# VactrolMixer.net
KiCad netlist of a schematic drawn in EAGLE
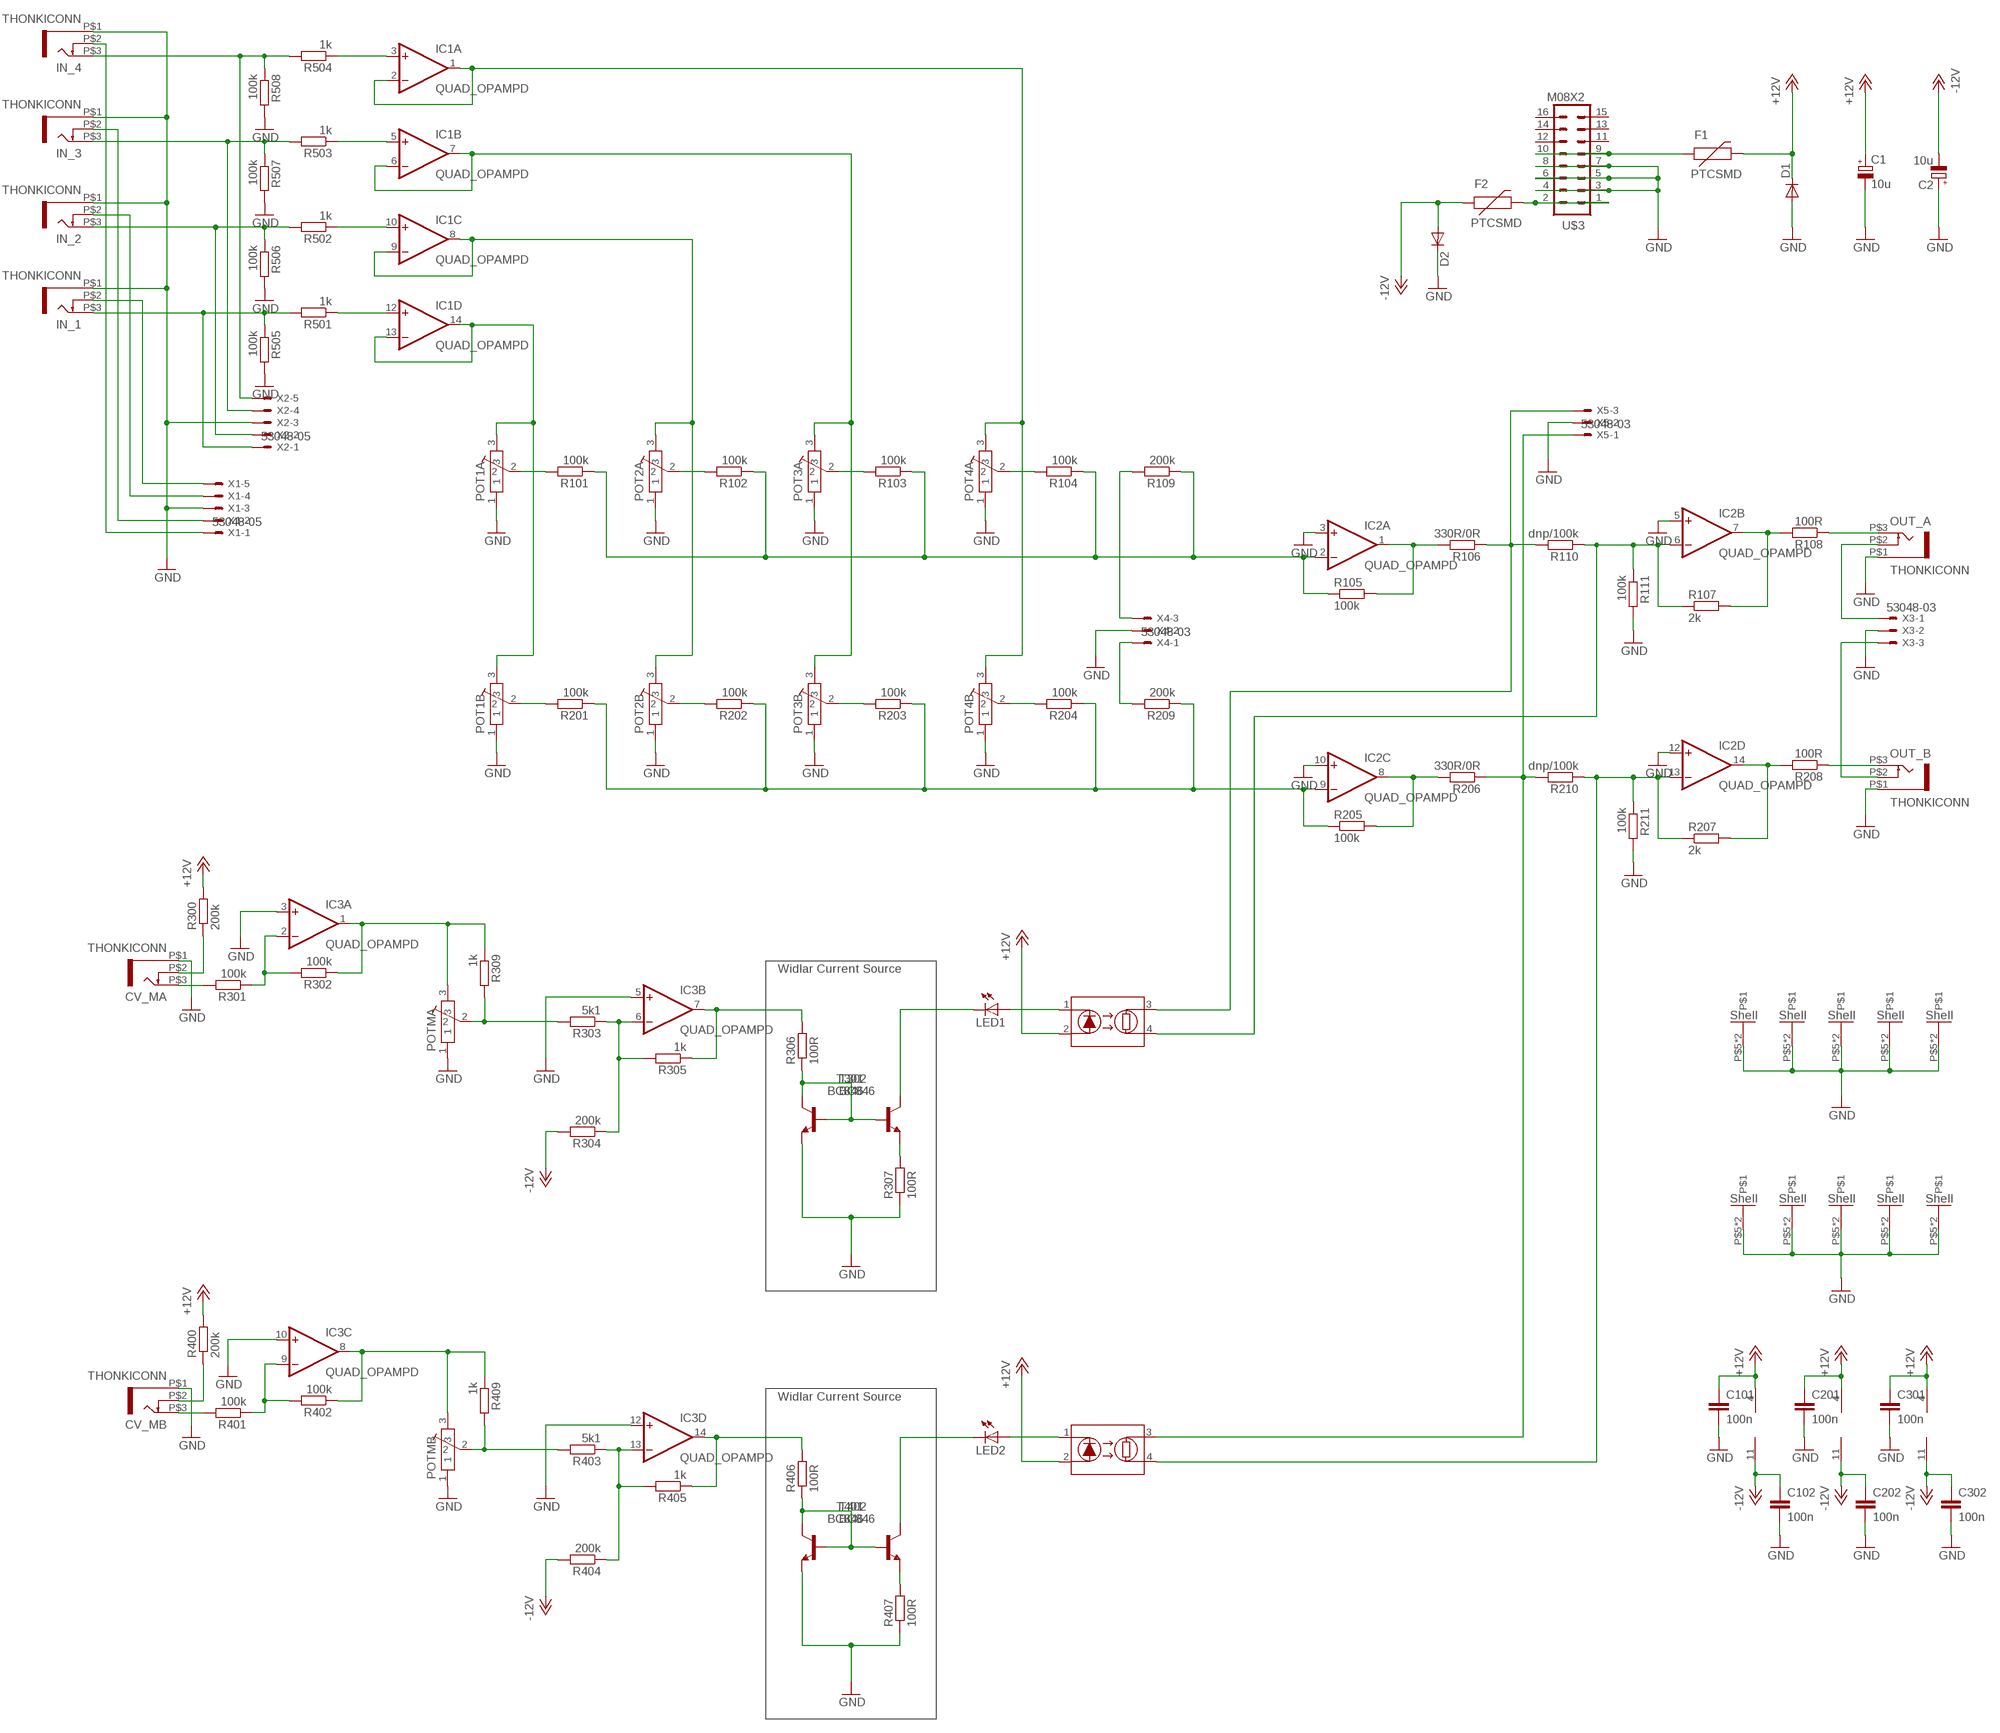
[diagram p0: schematic, sheet 1]

(export (version "E")
  (design (tool "Eeschema 10.0.6"))
  (components
    (comp (ref "C1")
      (value "10u")
      (footprint "eagle-import:153CLV-0605")
      (libsource (lib "eagle-import") (part "CPOL-EU153CLV-0605"))
    )
    (comp (ref "C2")
      (value "10u")
      (footprint "eagle-import:153CLV-0605")
      (libsource (lib "eagle-import") (part "CPOL-EU153CLV-0605"))
    )
    (comp (ref "C101")
      (value "100n")
      (footprint "eagle-import:C0603")
      (libsource (lib "eagle-import") (part "C-EUC0603"))
    )
    (comp (ref "C102")
      (value "100n")
      (footprint "eagle-import:C0603")
      (libsource (lib "eagle-import") (part "C-EUC0603"))
    )
    (comp (ref "C201")
      (value "100n")
      (footprint "eagle-import:C0603")
      (libsource (lib "eagle-import") (part "C-EUC0603"))
    )
    (comp (ref "C202")
      (value "100n")
      (footprint "eagle-import:C0603")
      (libsource (lib "eagle-import") (part "C-EUC0603"))
    )
    (comp (ref "C301")
      (value "100n")
      (footprint "eagle-import:C0603")
      (libsource (lib "eagle-import") (part "C-EUC0603"))
    )
    (comp (ref "C302")
      (value "100n")
      (footprint "eagle-import:C0603")
      (libsource (lib "eagle-import") (part "C-EUC0603"))
    )
    (comp (ref "CV_MA")
      (value "THONKICONN")
      (footprint "eagle-import:THONKICONN")
      (libsource (lib "eagle-import") (part "THONKICONN"))
    )
    (comp (ref "CV_MB")
      (value "THONKICONN")
      (footprint "eagle-import:THONKICONN")
      (libsource (lib "eagle-import") (part "THONKICONN"))
    )
    (comp (ref "D1")
      (value "DIODESMA")
      (footprint "eagle-import:SMA-DIODE")
      (libsource (lib "eagle-import") (part "DIODESMA"))
    )
    (comp (ref "D2")
      (value "DIODESMA")
      (footprint "eagle-import:SMA-DIODE")
      (libsource (lib "eagle-import") (part "DIODESMA"))
    )
    (comp (ref "F1")
      (value "PTCSMD")
      (footprint "eagle-import:PTC-1206")
      (libsource (lib "eagle-import") (part "PTCSMD"))
    )
    (comp (ref "F2")
      (value "PTCSMD")
      (footprint "eagle-import:PTC-1206")
      (libsource (lib "eagle-import") (part "PTCSMD"))
    )
    (comp (ref "IC1")
      (value "QUAD_OPAMPD")
      (footprint "eagle-import:SO14")
      (libsource (lib "eagle-import") (part "QUAD_OPAMPD"))
    )
    (comp (ref "IC2")
      (value "QUAD_OPAMPD")
      (footprint "eagle-import:SO14")
      (libsource (lib "eagle-import") (part "QUAD_OPAMPD"))
    )
    (comp (ref "IC3")
      (value "QUAD_OPAMPD")
      (footprint "eagle-import:SO14")
      (libsource (lib "eagle-import") (part "QUAD_OPAMPD"))
    )
    (comp (ref "IN_1")
      (value "THONKICONN")
      (footprint "eagle-import:THONKICONN")
      (libsource (lib "eagle-import") (part "THONKICONN"))
    )
    (comp (ref "IN_2")
      (value "THONKICONN")
      (footprint "eagle-import:THONKICONN")
      (libsource (lib "eagle-import") (part "THONKICONN"))
    )
    (comp (ref "IN_3")
      (value "THONKICONN")
      (footprint "eagle-import:THONKICONN")
      (libsource (lib "eagle-import") (part "THONKICONN"))
    )
    (comp (ref "IN_4")
      (value "THONKICONN")
      (footprint "eagle-import:THONKICONN")
      (libsource (lib "eagle-import") (part "THONKICONN"))
    )
    (comp (ref "LED1")
      (value "LED3MM")
      (footprint "eagle-import:LED3MM")
      (libsource (lib "eagle-import") (part "LED3MM"))
    )
    (comp (ref "LED2")
      (value "LED3MM")
      (footprint "eagle-import:LED3MM")
      (libsource (lib "eagle-import") (part "LED3MM"))
    )
    (comp (ref "OUT_A")
      (value "THONKICONN")
      (footprint "eagle-import:THONKICONN")
      (libsource (lib "eagle-import") (part "THONKICONN"))
    )
    (comp (ref "OUT_B")
      (value "THONKICONN")
      (footprint "eagle-import:THONKICONN")
      (libsource (lib "eagle-import") (part "THONKICONN"))
    )
    (comp (ref "POT1A")
      (value "POT-ALPS-RK09L1140")
      (footprint "eagle-import:POT-ALPS-RK09L1140")
      (libsource (lib "eagle-import") (part "POT-ALPS-RK09L1140"))
    )
    (comp (ref "POT1B")
      (value "POT-ALPS-RK09L1140")
      (footprint "eagle-import:POT-ALPS-RK09L1140")
      (libsource (lib "eagle-import") (part "POT-ALPS-RK09L1140"))
    )
    (comp (ref "POT2A")
      (value "POT-ALPS-RK09L1140")
      (footprint "eagle-import:POT-ALPS-RK09L1140")
      (libsource (lib "eagle-import") (part "POT-ALPS-RK09L1140"))
    )
    (comp (ref "POT2B")
      (value "POT-ALPS-RK09L1140")
      (footprint "eagle-import:POT-ALPS-RK09L1140")
      (libsource (lib "eagle-import") (part "POT-ALPS-RK09L1140"))
    )
    (comp (ref "POT3A")
      (value "POT-ALPS-RK09L1140")
      (footprint "eagle-import:POT-ALPS-RK09L1140")
      (libsource (lib "eagle-import") (part "POT-ALPS-RK09L1140"))
    )
    (comp (ref "POT3B")
      (value "POT-ALPS-RK09L1140")
      (footprint "eagle-import:POT-ALPS-RK09L1140")
      (libsource (lib "eagle-import") (part "POT-ALPS-RK09L1140"))
    )
    (comp (ref "POT4A")
      (value "POT-ALPS-RK09L1140")
      (footprint "eagle-import:POT-ALPS-RK09L1140")
      (libsource (lib "eagle-import") (part "POT-ALPS-RK09L1140"))
    )
    (comp (ref "POT4B")
      (value "POT-ALPS-RK09L1140")
      (footprint "eagle-import:POT-ALPS-RK09L1140")
      (libsource (lib "eagle-import") (part "POT-ALPS-RK09L1140"))
    )
    (comp (ref "POTMA")
      (value "POT-ALPS-RK09L1140")
      (footprint "eagle-import:POT-ALPS-RK09L1140")
      (libsource (lib "eagle-import") (part "POT-ALPS-RK09L1140"))
    )
    (comp (ref "POTMB")
      (value "POT-ALPS-RK09L1140")
      (footprint "eagle-import:POT-ALPS-RK09L1140")
      (libsource (lib "eagle-import") (part "POT-ALPS-RK09L1140"))
    )
    (comp (ref "R101")
      (value "100k")
      (footprint "eagle-import:R0603")
      (libsource (lib "eagle-import") (part "R-EU_R0603"))
    )
    (comp (ref "R102")
      (value "100k")
      (footprint "eagle-import:R0603")
      (libsource (lib "eagle-import") (part "R-EU_R0603"))
    )
    (comp (ref "R103")
      (value "100k")
      (footprint "eagle-import:R0603")
      (libsource (lib "eagle-import") (part "R-EU_R0603"))
    )
    (comp (ref "R104")
      (value "100k")
      (footprint "eagle-import:R0603")
      (libsource (lib "eagle-import") (part "R-EU_R0603"))
    )
    (comp (ref "R105")
      (value "100k")
      (footprint "eagle-import:R0603")
      (libsource (lib "eagle-import") (part "R-EU_R0603"))
    )
    (comp (ref "R106")
      (value "330R/0R")
      (footprint "eagle-import:R0603")
      (libsource (lib "eagle-import") (part "R-EU_R0603"))
    )
    (comp (ref "R107")
      (value "2k")
      (footprint "eagle-import:R0603")
      (libsource (lib "eagle-import") (part "R-EU_R0603"))
    )
    (comp (ref "R108")
      (value "100R")
      (footprint "eagle-import:R0603")
      (libsource (lib "eagle-import") (part "R-EU_R0603"))
    )
    (comp (ref "R109")
      (value "200k")
      (footprint "eagle-import:R0603")
      (libsource (lib "eagle-import") (part "R-EU_R0603"))
    )
    (comp (ref "R110")
      (value "dnp/100k")
      (footprint "eagle-import:R0603")
      (libsource (lib "eagle-import") (part "R-EU_R0603"))
    )
    (comp (ref "R111")
      (value "100k")
      (footprint "eagle-import:R0603")
      (libsource (lib "eagle-import") (part "R-EU_R0603"))
    )
    (comp (ref "R201")
      (value "100k")
      (footprint "eagle-import:R0603")
      (libsource (lib "eagle-import") (part "R-EU_R0603"))
    )
    (comp (ref "R202")
      (value "100k")
      (footprint "eagle-import:R0603")
      (libsource (lib "eagle-import") (part "R-EU_R0603"))
    )
    (comp (ref "R203")
      (value "100k")
      (footprint "eagle-import:R0603")
      (libsource (lib "eagle-import") (part "R-EU_R0603"))
    )
    (comp (ref "R204")
      (value "100k")
      (footprint "eagle-import:R0603")
      (libsource (lib "eagle-import") (part "R-EU_R0603"))
    )
    (comp (ref "R205")
      (value "100k")
      (footprint "eagle-import:R0603")
      (libsource (lib "eagle-import") (part "R-EU_R0603"))
    )
    (comp (ref "R206")
      (value "330R/0R")
      (footprint "eagle-import:R0603")
      (libsource (lib "eagle-import") (part "R-EU_R0603"))
    )
    (comp (ref "R207")
      (value "2k")
      (footprint "eagle-import:R0603")
      (libsource (lib "eagle-import") (part "R-EU_R0603"))
    )
    (comp (ref "R208")
      (value "100R")
      (footprint "eagle-import:R0603")
      (libsource (lib "eagle-import") (part "R-EU_R0603"))
    )
    (comp (ref "R209")
      (value "200k")
      (footprint "eagle-import:R0603")
      (libsource (lib "eagle-import") (part "R-EU_R0603"))
    )
    (comp (ref "R210")
      (value "dnp/100k")
      (footprint "eagle-import:R0603")
      (libsource (lib "eagle-import") (part "R-EU_R0603"))
    )
    (comp (ref "R211")
      (value "100k")
      (footprint "eagle-import:R0603")
      (libsource (lib "eagle-import") (part "R-EU_R0603"))
    )
    (comp (ref "R300")
      (value "200k")
      (footprint "eagle-import:R0603")
      (libsource (lib "eagle-import") (part "R-EU_R0603"))
    )
    (comp (ref "R301")
      (value "100k")
      (footprint "eagle-import:R0603")
      (libsource (lib "eagle-import") (part "R-EU_R0603"))
    )
    (comp (ref "R302")
      (value "100k")
      (footprint "eagle-import:R0603")
      (libsource (lib "eagle-import") (part "R-EU_R0603"))
    )
    (comp (ref "R303")
      (value "5k1")
      (footprint "eagle-import:R0603")
      (libsource (lib "eagle-import") (part "R-EU_R0603"))
    )
    (comp (ref "R304")
      (value "200k")
      (footprint "eagle-import:R0603")
      (libsource (lib "eagle-import") (part "R-EU_R0603"))
    )
    (comp (ref "R305")
      (value "1k")
      (footprint "eagle-import:R0603")
      (libsource (lib "eagle-import") (part "R-EU_R0603"))
    )
    (comp (ref "R306")
      (value "100R")
      (footprint "eagle-import:R0603")
      (libsource (lib "eagle-import") (part "R-EU_R0603"))
    )
    (comp (ref "R307")
      (value "100R")
      (footprint "eagle-import:R0603")
      (libsource (lib "eagle-import") (part "R-EU_R0603"))
    )
    (comp (ref "R309")
      (value "1k")
      (footprint "eagle-import:R0603")
      (libsource (lib "eagle-import") (part "R-EU_R0603"))
    )
    (comp (ref "R400")
      (value "200k")
      (footprint "eagle-import:R0603")
      (libsource (lib "eagle-import") (part "R-EU_R0603"))
    )
    (comp (ref "R401")
      (value "100k")
      (footprint "eagle-import:R0603")
      (libsource (lib "eagle-import") (part "R-EU_R0603"))
    )
    (comp (ref "R402")
      (value "100k")
      (footprint "eagle-import:R0603")
      (libsource (lib "eagle-import") (part "R-EU_R0603"))
    )
    (comp (ref "R403")
      (value "5k1")
      (footprint "eagle-import:R0603")
      (libsource (lib "eagle-import") (part "R-EU_R0603"))
    )
    (comp (ref "R404")
      (value "200k")
      (footprint "eagle-import:R0603")
      (libsource (lib "eagle-import") (part "R-EU_R0603"))
    )
    (comp (ref "R405")
      (value "1k")
      (footprint "eagle-import:R0603")
      (libsource (lib "eagle-import") (part "R-EU_R0603"))
    )
    (comp (ref "R406")
      (value "100R")
      (footprint "eagle-import:R0603")
      (libsource (lib "eagle-import") (part "R-EU_R0603"))
    )
    (comp (ref "R407")
      (value "100R")
      (footprint "eagle-import:R0603")
      (libsource (lib "eagle-import") (part "R-EU_R0603"))
    )
    (comp (ref "R409")
      (value "1k")
      (footprint "eagle-import:R0603")
      (libsource (lib "eagle-import") (part "R-EU_R0603"))
    )
    (comp (ref "R501")
      (value "1k")
      (footprint "eagle-import:R0603")
      (libsource (lib "eagle-import") (part "R-EU_R0603"))
    )
    (comp (ref "R502")
      (value "1k")
      (footprint "eagle-import:R0603")
      (libsource (lib "eagle-import") (part "R-EU_R0603"))
    )
    (comp (ref "R503")
      (value "1k")
      (footprint "eagle-import:R0603")
      (libsource (lib "eagle-import") (part "R-EU_R0603"))
    )
    (comp (ref "R504")
      (value "1k")
      (footprint "eagle-import:R0603")
      (libsource (lib "eagle-import") (part "R-EU_R0603"))
    )
    (comp (ref "R505")
      (value "100k")
      (footprint "eagle-import:R0603")
      (libsource (lib "eagle-import") (part "R-EU_R0603"))
    )
    (comp (ref "R506")
      (value "100k")
      (footprint "eagle-import:R0603")
      (libsource (lib "eagle-import") (part "R-EU_R0603"))
    )
    (comp (ref "R507")
      (value "100k")
      (footprint "eagle-import:R0603")
      (libsource (lib "eagle-import") (part "R-EU_R0603"))
    )
    (comp (ref "R508")
      (value "100k")
      (footprint "eagle-import:R0603")
      (libsource (lib "eagle-import") (part "R-EU_R0603"))
    )
    (comp (ref "T301")
      (value "BC846")
      (footprint "eagle-import:SOT23")
      (libsource (lib "eagle-import") (part "BC846"))
    )
    (comp (ref "T302")
      (value "BC846")
      (footprint "eagle-import:SOT23")
      (libsource (lib "eagle-import") (part "BC846"))
    )
    (comp (ref "T401")
      (value "BC846")
      (footprint "eagle-import:SOT23")
      (libsource (lib "eagle-import") (part "BC846"))
    )
    (comp (ref "T402")
      (value "BC846")
      (footprint "eagle-import:SOT23")
      (libsource (lib "eagle-import") (part "BC846"))
    )
    (comp (ref "U$3")
      (value "M08X2")
      (footprint "eagle-import:2X8")
      (libsource (lib "eagle-import") (part "M08X2"))
    )
    (comp (ref "VAC1")
      (value "VTL5C3")
      (footprint "eagle-import:VTL5C3")
      (libsource (lib "eagle-import") (part "VTL5C3"))
    )
    (comp (ref "VAC2")
      (value "VTL5C3")
      (footprint "eagle-import:VTL5C3")
      (libsource (lib "eagle-import") (part "VTL5C3"))
    )
    (comp (ref "X1")
      (value "53048-05")
      (footprint "eagle-import:53048-05")
      (fields (field (name "MF") "MOLEX") (field (name "MPN") "53048-0510"))
      (libsource (lib "eagle-import") (part "53?-05048"))
    )
    (comp (ref "X2")
      (value "53048-05")
      (footprint "eagle-import:53048-05")
      (fields (field (name "MF") "MOLEX") (field (name "MPN") "53048-0510"))
      (libsource (lib "eagle-import") (part "53?-05048"))
    )
    (comp (ref "X3")
      (value "53048-03")
      (footprint "eagle-import:53048-03")
      (fields (field (name "MF") "WALDOM/MOLEX") (field (name "MPN") "53048-0310"))
      (libsource (lib "eagle-import") (part "53?-03048"))
    )
    (comp (ref "X4")
      (value "53048-03")
      (footprint "eagle-import:53048-03")
      (fields (field (name "MF") "WALDOM/MOLEX") (field (name "MPN") "53048-0310"))
      (libsource (lib "eagle-import") (part "53?-03048"))
    )
    (comp (ref "X5")
      (value "53048-03")
      (footprint "eagle-import:53048-03")
      (fields (field (name "MF") "WALDOM/MOLEX") (field (name "MPN") "53048-0310"))
      (libsource (lib "eagle-import") (part "53?-03048"))
    )
  )
  (nets
    (net (code "1") (name "+12V") (class "Default")
      (node (ref "C1") (pin "+") (pinfunction "+_+") (pintype "passive"))
      (node (ref "C101") (pin "1") (pinfunction "1_1") (pintype "passive"))
      (node (ref "C201") (pin "1") (pinfunction "1_1") (pintype "passive"))
      (node (ref "C301") (pin "1") (pinfunction "1_1") (pintype "passive"))
      (node (ref "D1") (pin "C") (pinfunction "C_C") (pintype "passive"))
      (node (ref "F1") (pin "2") (pinfunction "2_2") (pintype "bidirectional"))
      (node (ref "IC1") (pin "4") (pinfunction "V+_4") (pintype "power_in"))
      (node (ref "IC2") (pin "4") (pinfunction "V+_4") (pintype "power_in"))
      (node (ref "IC3") (pin "4") (pinfunction "V+_4") (pintype "power_in"))
      (node (ref "R300") (pin "2") (pinfunction "2_2") (pintype "passive"))
      (node (ref "R400") (pin "2") (pinfunction "2_2") (pintype "passive"))
      (node (ref "VAC1") (pin "2") (pinfunction "LED+_2") (pintype "bidirectional"))
      (node (ref "VAC2") (pin "2") (pinfunction "LED+_2") (pintype "bidirectional"))
    )
    (net (code "2") (name "-12V") (class "Default")
      (node (ref "C102") (pin "1") (pinfunction "1_1") (pintype "passive"))
      (node (ref "C2") (pin "-") (pinfunction "-_-") (pintype "passive"))
      (node (ref "C202") (pin "1") (pinfunction "1_1") (pintype "passive"))
      (node (ref "C302") (pin "1") (pinfunction "1_1") (pintype "passive"))
      (node (ref "D2") (pin "A") (pinfunction "A_A") (pintype "passive"))
      (node (ref "F2") (pin "1") (pinfunction "1_1") (pintype "bidirectional"))
      (node (ref "IC1") (pin "11") (pinfunction "V-_11") (pintype "power_in"))
      (node (ref "IC2") (pin "11") (pinfunction "V-_11") (pintype "power_in"))
      (node (ref "IC3") (pin "11") (pinfunction "V-_11") (pintype "power_in"))
      (node (ref "R304") (pin "2") (pinfunction "2_2") (pintype "passive"))
      (node (ref "R404") (pin "2") (pinfunction "2_2") (pintype "passive"))
    )
    (net (code "3") (name "GND") (class "Default")
      (node (ref "C1") (pin "-") (pinfunction "-_-") (pintype "passive"))
      (node (ref "C101") (pin "2") (pinfunction "2_2") (pintype "passive"))
      (node (ref "C102") (pin "2") (pinfunction "2_2") (pintype "passive"))
      (node (ref "C2") (pin "+") (pinfunction "+_+") (pintype "passive"))
      (node (ref "C201") (pin "2") (pinfunction "2_2") (pintype "passive"))
      (node (ref "C202") (pin "2") (pinfunction "2_2") (pintype "passive"))
      (node (ref "C301") (pin "2") (pinfunction "2_2") (pintype "passive"))
      (node (ref "C302") (pin "2") (pinfunction "2_2") (pintype "passive"))
      (node (ref "CV_MA") (pin "P$1") (pinfunction "5_P$1") (pintype "passive"))
      (node (ref "CV_MB") (pin "P$1") (pinfunction "5_P$1") (pintype "passive"))
      (node (ref "D1") (pin "A") (pinfunction "A_A") (pintype "passive"))
      (node (ref "D2") (pin "C") (pinfunction "C_C") (pintype "passive"))
      (node (ref "IC2") (pin "10") (pinfunction "+IN_10") (pintype "input"))
      (node (ref "IC2") (pin "12") (pinfunction "+IN_12") (pintype "input"))
      (node (ref "IC2") (pin "3") (pinfunction "+IN_3") (pintype "input"))
      (node (ref "IC2") (pin "5") (pinfunction "+IN_5") (pintype "input"))
      (node (ref "IC3") (pin "10") (pinfunction "+IN_10") (pintype "input"))
      (node (ref "IC3") (pin "12") (pinfunction "+IN_12") (pintype "input"))
      (node (ref "IC3") (pin "3") (pinfunction "+IN_3") (pintype "input"))
      (node (ref "IC3") (pin "5") (pinfunction "+IN_5") (pintype "input"))
      (node (ref "IN_1") (pin "P$1") (pinfunction "5_P$1") (pintype "passive"))
      (node (ref "IN_2") (pin "P$1") (pinfunction "5_P$1") (pintype "passive"))
      (node (ref "IN_3") (pin "P$1") (pinfunction "5_P$1") (pintype "passive"))
      (node (ref "IN_4") (pin "P$1") (pinfunction "5_P$1") (pintype "passive"))
      (node (ref "OUT_A") (pin "P$1") (pinfunction "5_P$1") (pintype "passive"))
      (node (ref "OUT_B") (pin "P$1") (pinfunction "5_P$1") (pintype "passive"))
      (node (ref "POT1A") (pin "1") (pinfunction "1_1") (pintype "bidirectional"))
      (node (ref "POT1A") (pin "P$5") (pinfunction "P$1_P$5") (pintype "bidirectional"))
      (node (ref "POT1A") (pin "P$6") (pinfunction "P$1_P$6") (pintype "bidirectional"))
      (node (ref "POT1B") (pin "1") (pinfunction "1_1") (pintype "bidirectional"))
      (node (ref "POT1B") (pin "P$5") (pinfunction "P$1_P$5") (pintype "bidirectional"))
      (node (ref "POT1B") (pin "P$6") (pinfunction "P$1_P$6") (pintype "bidirectional"))
      (node (ref "POT2A") (pin "1") (pinfunction "1_1") (pintype "bidirectional"))
      (node (ref "POT2A") (pin "P$5") (pinfunction "P$1_P$5") (pintype "bidirectional"))
      (node (ref "POT2A") (pin "P$6") (pinfunction "P$1_P$6") (pintype "bidirectional"))
      (node (ref "POT2B") (pin "1") (pinfunction "1_1") (pintype "bidirectional"))
      (node (ref "POT2B") (pin "P$5") (pinfunction "P$1_P$5") (pintype "bidirectional"))
      (node (ref "POT2B") (pin "P$6") (pinfunction "P$1_P$6") (pintype "bidirectional"))
      (node (ref "POT3A") (pin "1") (pinfunction "1_1") (pintype "bidirectional"))
      (node (ref "POT3A") (pin "P$5") (pinfunction "P$1_P$5") (pintype "bidirectional"))
      (node (ref "POT3A") (pin "P$6") (pinfunction "P$1_P$6") (pintype "bidirectional"))
      (node (ref "POT3B") (pin "1") (pinfunction "1_1") (pintype "bidirectional"))
      (node (ref "POT3B") (pin "P$5") (pinfunction "P$1_P$5") (pintype "bidirectional"))
      (node (ref "POT3B") (pin "P$6") (pinfunction "P$1_P$6") (pintype "bidirectional"))
      (node (ref "POT4A") (pin "1") (pinfunction "1_1") (pintype "bidirectional"))
      (node (ref "POT4A") (pin "P$5") (pinfunction "P$1_P$5") (pintype "bidirectional"))
      (node (ref "POT4A") (pin "P$6") (pinfunction "P$1_P$6") (pintype "bidirectional"))
      (node (ref "POT4B") (pin "1") (pinfunction "1_1") (pintype "bidirectional"))
      (node (ref "POT4B") (pin "P$5") (pinfunction "P$1_P$5") (pintype "bidirectional"))
      (node (ref "POT4B") (pin "P$6") (pinfunction "P$1_P$6") (pintype "bidirectional"))
      (node (ref "POTMA") (pin "1") (pinfunction "1_1") (pintype "bidirectional"))
      (node (ref "POTMA") (pin "P$5") (pinfunction "P$1_P$5") (pintype "bidirectional"))
      (node (ref "POTMA") (pin "P$6") (pinfunction "P$1_P$6") (pintype "bidirectional"))
      (node (ref "POTMB") (pin "1") (pinfunction "1_1") (pintype "bidirectional"))
      (node (ref "POTMB") (pin "P$5") (pinfunction "P$1_P$5") (pintype "bidirectional"))
      (node (ref "POTMB") (pin "P$6") (pinfunction "P$1_P$6") (pintype "bidirectional"))
      (node (ref "R111") (pin "2") (pinfunction "2_2") (pintype "passive"))
      (node (ref "R211") (pin "2") (pinfunction "2_2") (pintype "passive"))
      (node (ref "R307") (pin "1") (pinfunction "1_1") (pintype "passive"))
      (node (ref "R407") (pin "1") (pinfunction "1_1") (pintype "passive"))
      (node (ref "R505") (pin "2") (pinfunction "2_2") (pintype "passive"))
      (node (ref "R506") (pin "2") (pinfunction "2_2") (pintype "passive"))
      (node (ref "R507") (pin "2") (pinfunction "2_2") (pintype "passive"))
      (node (ref "R508") (pin "2") (pinfunction "2_2") (pintype "passive"))
      (node (ref "T301") (pin "2") (pinfunction "E_2") (pintype "passive"))
      (node (ref "T401") (pin "2") (pinfunction "E_2") (pintype "passive"))
      (node (ref "U$3") (pin "3") (pinfunction "3_3") (pintype "passive"))
      (node (ref "U$3") (pin "4") (pinfunction "4_4") (pintype "passive"))
      (node (ref "U$3") (pin "5") (pinfunction "5_5") (pintype "passive"))
      (node (ref "U$3") (pin "6") (pinfunction "6_6") (pintype "passive"))
      (node (ref "U$3") (pin "7") (pinfunction "7_7") (pintype "passive"))
      (node (ref "U$3") (pin "8") (pinfunction "8_8") (pintype "passive"))
      (node (ref "X1") (pin "3") (pinfunction "S_3") (pintype "passive"))
      (node (ref "X2") (pin "3") (pinfunction "S_3") (pintype "passive"))
      (node (ref "X3") (pin "2") (pinfunction "S_2") (pintype "passive"))
      (node (ref "X4") (pin "2") (pinfunction "S_2") (pintype "passive"))
      (node (ref "X5") (pin "2") (pinfunction "S_2") (pintype "passive"))
    )
    (net (code "4") (name "Net-(CV_MA-3)") (class "Default")
      (node (ref "CV_MA") (pin "P$3") (pinfunction "3_P$3") (pintype "passive"))
      (node (ref "R301") (pin "2") (pinfunction "2_2") (pintype "passive"))
    )
    (net (code "5") (name "Net-(CV_MA-4)") (class "Default")
      (node (ref "CV_MA") (pin "P$2") (pinfunction "4_P$2") (pintype "passive"))
      (node (ref "R300") (pin "1") (pinfunction "1_1") (pintype "passive"))
    )
    (net (code "6") (name "Net-(CV_MB-3)") (class "Default")
      (node (ref "CV_MB") (pin "P$3") (pinfunction "3_P$3") (pintype "passive"))
      (node (ref "R401") (pin "2") (pinfunction "2_2") (pintype "passive"))
    )
    (net (code "7") (name "Net-(CV_MB-4)") (class "Default")
      (node (ref "CV_MB") (pin "P$2") (pinfunction "4_P$2") (pintype "passive"))
      (node (ref "R400") (pin "1") (pinfunction "1_1") (pintype "passive"))
    )
    (net (code "8") (name "Net-(F1-Pad1)") (class "Default")
      (node (ref "F1") (pin "1") (pinfunction "1_1") (pintype "bidirectional"))
      (node (ref "U$3") (pin "10") (pinfunction "10_10") (pintype "passive"))
      (node (ref "U$3") (pin "9") (pinfunction "9_9") (pintype "passive"))
    )
    (net (code "9") (name "Net-(F2-Pad2)") (class "Default")
      (node (ref "F2") (pin "2") (pinfunction "2_2") (pintype "bidirectional"))
      (node (ref "U$3") (pin "1") (pinfunction "1_1") (pintype "passive"))
      (node (ref "U$3") (pin "2") (pinfunction "2_2") (pintype "passive"))
    )
    (net (code "10") (name "Net-(IC1A-+IN)") (class "Default")
      (node (ref "IC1") (pin "3") (pinfunction "+IN_3") (pintype "input"))
      (node (ref "R504") (pin "1") (pinfunction "1_1") (pintype "passive"))
    )
    (net (code "11") (name "Net-(IC1A--IN)") (class "Default")
      (node (ref "IC1") (pin "1") (pinfunction "OUT_1") (pintype "output"))
      (node (ref "IC1") (pin "2") (pinfunction "-IN_2") (pintype "input"))
      (node (ref "POT4A") (pin "3") (pinfunction "3_3") (pintype "bidirectional"))
      (node (ref "POT4B") (pin "3") (pinfunction "3_3") (pintype "bidirectional"))
    )
    (net (code "12") (name "Net-(IC1B-+IN)") (class "Default")
      (node (ref "IC1") (pin "5") (pinfunction "+IN_5") (pintype "input"))
      (node (ref "R503") (pin "1") (pinfunction "1_1") (pintype "passive"))
    )
    (net (code "13") (name "Net-(IC1B--IN)") (class "Default")
      (node (ref "IC1") (pin "6") (pinfunction "-IN_6") (pintype "input"))
      (node (ref "IC1") (pin "7") (pinfunction "OUT_7") (pintype "output"))
      (node (ref "POT3A") (pin "3") (pinfunction "3_3") (pintype "bidirectional"))
      (node (ref "POT3B") (pin "3") (pinfunction "3_3") (pintype "bidirectional"))
    )
    (net (code "14") (name "Net-(IC1C-+IN)") (class "Default")
      (node (ref "IC1") (pin "10") (pinfunction "+IN_10") (pintype "input"))
      (node (ref "R502") (pin "1") (pinfunction "1_1") (pintype "passive"))
    )
    (net (code "15") (name "Net-(IC1C--IN)") (class "Default")
      (node (ref "IC1") (pin "8") (pinfunction "OUT_8") (pintype "output"))
      (node (ref "IC1") (pin "9") (pinfunction "-IN_9") (pintype "input"))
      (node (ref "POT2A") (pin "3") (pinfunction "3_3") (pintype "bidirectional"))
      (node (ref "POT2B") (pin "3") (pinfunction "3_3") (pintype "bidirectional"))
    )
    (net (code "16") (name "Net-(IC1D-+IN)") (class "Default")
      (node (ref "IC1") (pin "12") (pinfunction "+IN_12") (pintype "input"))
      (node (ref "R501") (pin "1") (pinfunction "1_1") (pintype "passive"))
    )
    (net (code "17") (name "Net-(IC1D--IN)") (class "Default")
      (node (ref "IC1") (pin "13") (pinfunction "-IN_13") (pintype "input"))
      (node (ref "IC1") (pin "14") (pinfunction "OUT_14") (pintype "output"))
      (node (ref "POT1A") (pin "3") (pinfunction "3_3") (pintype "bidirectional"))
      (node (ref "POT1B") (pin "3") (pinfunction "3_3") (pintype "bidirectional"))
    )
    (net (code "18") (name "Net-(IC2A--IN)") (class "Default")
      (node (ref "IC2") (pin "2") (pinfunction "-IN_2") (pintype "input"))
      (node (ref "R101") (pin "1") (pinfunction "1_1") (pintype "passive"))
      (node (ref "R102") (pin "1") (pinfunction "1_1") (pintype "passive"))
      (node (ref "R103") (pin "1") (pinfunction "1_1") (pintype "passive"))
      (node (ref "R104") (pin "1") (pinfunction "1_1") (pintype "passive"))
      (node (ref "R105") (pin "1") (pinfunction "1_1") (pintype "passive"))
      (node (ref "R109") (pin "1") (pinfunction "1_1") (pintype "passive"))
    )
    (net (code "19") (name "Net-(IC2A-OUT)") (class "Default")
      (node (ref "IC2") (pin "1") (pinfunction "OUT_1") (pintype "output"))
      (node (ref "R105") (pin "2") (pinfunction "2_2") (pintype "passive"))
      (node (ref "R106") (pin "2") (pinfunction "2_2") (pintype "passive"))
    )
    (net (code "20") (name "Net-(IC2B--IN)") (class "Default")
      (node (ref "IC2") (pin "6") (pinfunction "-IN_6") (pintype "input"))
      (node (ref "R107") (pin "1") (pinfunction "1_1") (pintype "passive"))
      (node (ref "R110") (pin "1") (pinfunction "1_1") (pintype "passive"))
      (node (ref "R111") (pin "1") (pinfunction "1_1") (pintype "passive"))
      (node (ref "VAC1") (pin "4") (pinfunction "LDRB_4") (pintype "bidirectional"))
    )
    (net (code "21") (name "Net-(IC2B-OUT)") (class "Default")
      (node (ref "IC2") (pin "7") (pinfunction "OUT_7") (pintype "output"))
      (node (ref "R107") (pin "2") (pinfunction "2_2") (pintype "passive"))
      (node (ref "R108") (pin "2") (pinfunction "2_2") (pintype "passive"))
    )
    (net (code "22") (name "Net-(IC2C--IN)") (class "Default")
      (node (ref "IC2") (pin "9") (pinfunction "-IN_9") (pintype "input"))
      (node (ref "R201") (pin "1") (pinfunction "1_1") (pintype "passive"))
      (node (ref "R202") (pin "1") (pinfunction "1_1") (pintype "passive"))
      (node (ref "R203") (pin "1") (pinfunction "1_1") (pintype "passive"))
      (node (ref "R204") (pin "1") (pinfunction "1_1") (pintype "passive"))
      (node (ref "R205") (pin "1") (pinfunction "1_1") (pintype "passive"))
      (node (ref "R209") (pin "1") (pinfunction "1_1") (pintype "passive"))
    )
    (net (code "23") (name "Net-(IC2C-OUT)") (class "Default")
      (node (ref "IC2") (pin "8") (pinfunction "OUT_8") (pintype "output"))
      (node (ref "R205") (pin "2") (pinfunction "2_2") (pintype "passive"))
      (node (ref "R206") (pin "2") (pinfunction "2_2") (pintype "passive"))
    )
    (net (code "24") (name "Net-(IC2D--IN)") (class "Default")
      (node (ref "IC2") (pin "13") (pinfunction "-IN_13") (pintype "input"))
      (node (ref "R207") (pin "1") (pinfunction "1_1") (pintype "passive"))
      (node (ref "R210") (pin "1") (pinfunction "1_1") (pintype "passive"))
      (node (ref "R211") (pin "1") (pinfunction "1_1") (pintype "passive"))
      (node (ref "VAC2") (pin "4") (pinfunction "LDRB_4") (pintype "bidirectional"))
    )
    (net (code "25") (name "Net-(IC2D-OUT)") (class "Default")
      (node (ref "IC2") (pin "14") (pinfunction "OUT_14") (pintype "output"))
      (node (ref "R207") (pin "2") (pinfunction "2_2") (pintype "passive"))
      (node (ref "R208") (pin "2") (pinfunction "2_2") (pintype "passive"))
    )
    (net (code "26") (name "Net-(IC3A--IN)") (class "Default")
      (node (ref "IC3") (pin "2") (pinfunction "-IN_2") (pintype "input"))
      (node (ref "R301") (pin "1") (pinfunction "1_1") (pintype "passive"))
      (node (ref "R302") (pin "2") (pinfunction "2_2") (pintype "passive"))
    )
    (net (code "27") (name "Net-(IC3A-OUT)") (class "Default")
      (node (ref "IC3") (pin "1") (pinfunction "OUT_1") (pintype "output"))
      (node (ref "POTMA") (pin "3") (pinfunction "3_3") (pintype "bidirectional"))
      (node (ref "R302") (pin "1") (pinfunction "1_1") (pintype "passive"))
      (node (ref "R309") (pin "1") (pinfunction "1_1") (pintype "passive"))
    )
    (net (code "28") (name "Net-(IC3B--IN)") (class "Default")
      (node (ref "IC3") (pin "6") (pinfunction "-IN_6") (pintype "input"))
      (node (ref "R303") (pin "1") (pinfunction "1_1") (pintype "passive"))
      (node (ref "R304") (pin "1") (pinfunction "1_1") (pintype "passive"))
      (node (ref "R305") (pin "2") (pinfunction "2_2") (pintype "passive"))
    )
    (net (code "29") (name "Net-(IC3B-OUT)") (class "Default")
      (node (ref "IC3") (pin "7") (pinfunction "OUT_7") (pintype "output"))
      (node (ref "R305") (pin "1") (pinfunction "1_1") (pintype "passive"))
      (node (ref "R306") (pin "2") (pinfunction "2_2") (pintype "passive"))
    )
    (net (code "30") (name "Net-(IC3C--IN)") (class "Default")
      (node (ref "IC3") (pin "9") (pinfunction "-IN_9") (pintype "input"))
      (node (ref "R401") (pin "1") (pinfunction "1_1") (pintype "passive"))
      (node (ref "R402") (pin "2") (pinfunction "2_2") (pintype "passive"))
    )
    (net (code "31") (name "Net-(IC3C-OUT)") (class "Default")
      (node (ref "IC3") (pin "8") (pinfunction "OUT_8") (pintype "output"))
      (node (ref "POTMB") (pin "3") (pinfunction "3_3") (pintype "bidirectional"))
      (node (ref "R402") (pin "1") (pinfunction "1_1") (pintype "passive"))
      (node (ref "R409") (pin "1") (pinfunction "1_1") (pintype "passive"))
    )
    (net (code "32") (name "Net-(IC3D--IN)") (class "Default")
      (node (ref "IC3") (pin "13") (pinfunction "-IN_13") (pintype "input"))
      (node (ref "R403") (pin "1") (pinfunction "1_1") (pintype "passive"))
      (node (ref "R404") (pin "1") (pinfunction "1_1") (pintype "passive"))
      (node (ref "R405") (pin "2") (pinfunction "2_2") (pintype "passive"))
    )
    (net (code "33") (name "Net-(IC3D-OUT)") (class "Default")
      (node (ref "IC3") (pin "14") (pinfunction "OUT_14") (pintype "output"))
      (node (ref "R405") (pin "1") (pinfunction "1_1") (pintype "passive"))
      (node (ref "R406") (pin "2") (pinfunction "2_2") (pintype "passive"))
    )
    (net (code "34") (name "Net-(IN_1-3)") (class "Default")
      (node (ref "IN_1") (pin "P$3") (pinfunction "3_P$3") (pintype "passive"))
      (node (ref "R501") (pin "2") (pinfunction "2_2") (pintype "passive"))
      (node (ref "R505") (pin "1") (pinfunction "1_1") (pintype "passive"))
      (node (ref "X2") (pin "1") (pinfunction "S_1") (pintype "passive"))
    )
    (net (code "35") (name "Net-(IN_1-4)") (class "Default")
      (node (ref "IN_1") (pin "P$2") (pinfunction "4_P$2") (pintype "passive"))
      (node (ref "X1") (pin "5") (pinfunction "S_5") (pintype "passive"))
    )
    (net (code "36") (name "Net-(IN_2-3)") (class "Default")
      (node (ref "IN_2") (pin "P$3") (pinfunction "3_P$3") (pintype "passive"))
      (node (ref "R502") (pin "2") (pinfunction "2_2") (pintype "passive"))
      (node (ref "R506") (pin "1") (pinfunction "1_1") (pintype "passive"))
      (node (ref "X2") (pin "2") (pinfunction "S_2") (pintype "passive"))
    )
    (net (code "37") (name "Net-(IN_2-4)") (class "Default")
      (node (ref "IN_2") (pin "P$2") (pinfunction "4_P$2") (pintype "passive"))
      (node (ref "X1") (pin "4") (pinfunction "S_4") (pintype "passive"))
    )
    (net (code "38") (name "Net-(IN_3-3)") (class "Default")
      (node (ref "IN_3") (pin "P$3") (pinfunction "3_P$3") (pintype "passive"))
      (node (ref "R503") (pin "2") (pinfunction "2_2") (pintype "passive"))
      (node (ref "R507") (pin "1") (pinfunction "1_1") (pintype "passive"))
      (node (ref "X2") (pin "4") (pinfunction "S_4") (pintype "passive"))
    )
    (net (code "39") (name "Net-(IN_3-4)") (class "Default")
      (node (ref "IN_3") (pin "P$2") (pinfunction "4_P$2") (pintype "passive"))
      (node (ref "X1") (pin "2") (pinfunction "S_2") (pintype "passive"))
    )
    (net (code "40") (name "Net-(IN_4-3)") (class "Default")
      (node (ref "IN_4") (pin "P$3") (pinfunction "3_P$3") (pintype "passive"))
      (node (ref "R504") (pin "2") (pinfunction "2_2") (pintype "passive"))
      (node (ref "R508") (pin "1") (pinfunction "1_1") (pintype "passive"))
      (node (ref "X2") (pin "5") (pinfunction "S_5") (pintype "passive"))
    )
    (net (code "41") (name "Net-(IN_4-4)") (class "Default")
      (node (ref "IN_4") (pin "P$2") (pinfunction "4_P$2") (pintype "passive"))
      (node (ref "X1") (pin "1") (pinfunction "S_1") (pintype "passive"))
    )
    (net (code "42") (name "Net-(LED1-C)") (class "Default")
      (node (ref "LED1") (pin "K") (pinfunction "C_K") (pintype "passive"))
      (node (ref "T302") (pin "3") (pinfunction "C_3") (pintype "passive"))
    )
    (net (code "43") (name "Net-(LED2-C)") (class "Default")
      (node (ref "LED2") (pin "K") (pinfunction "C_K") (pintype "passive"))
      (node (ref "T402") (pin "3") (pinfunction "C_3") (pintype "passive"))
    )
    (net (code "44") (name "Net-(OUT_A-3)") (class "Default")
      (node (ref "OUT_A") (pin "P$3") (pinfunction "3_P$3") (pintype "passive"))
      (node (ref "R108") (pin "1") (pinfunction "1_1") (pintype "passive"))
    )
    (net (code "45") (name "Net-(OUT_A-4)") (class "Default")
      (node (ref "OUT_A") (pin "P$2") (pinfunction "4_P$2") (pintype "passive"))
      (node (ref "X3") (pin "1") (pinfunction "S_1") (pintype "passive"))
    )
    (net (code "46") (name "Net-(OUT_B-3)") (class "Default")
      (node (ref "OUT_B") (pin "P$3") (pinfunction "3_P$3") (pintype "passive"))
      (node (ref "R208") (pin "1") (pinfunction "1_1") (pintype "passive"))
    )
    (net (code "47") (name "Net-(OUT_B-4)") (class "Default")
      (node (ref "OUT_B") (pin "P$2") (pinfunction "4_P$2") (pintype "passive"))
      (node (ref "X3") (pin "3") (pinfunction "S_3") (pintype "passive"))
    )
    (net (code "48") (name "Net-(POT1A-Pad2)") (class "Default")
      (node (ref "POT1A") (pin "2") (pinfunction "2_2") (pintype "bidirectional"))
      (node (ref "R101") (pin "2") (pinfunction "2_2") (pintype "passive"))
    )
    (net (code "49") (name "Net-(POT1B-Pad2)") (class "Default")
      (node (ref "POT1B") (pin "2") (pinfunction "2_2") (pintype "bidirectional"))
      (node (ref "R201") (pin "2") (pinfunction "2_2") (pintype "passive"))
    )
    (net (code "50") (name "Net-(POT2A-Pad2)") (class "Default")
      (node (ref "POT2A") (pin "2") (pinfunction "2_2") (pintype "bidirectional"))
      (node (ref "R102") (pin "2") (pinfunction "2_2") (pintype "passive"))
    )
    (net (code "51") (name "Net-(POT2B-Pad2)") (class "Default")
      (node (ref "POT2B") (pin "2") (pinfunction "2_2") (pintype "bidirectional"))
      (node (ref "R202") (pin "2") (pinfunction "2_2") (pintype "passive"))
    )
    (net (code "52") (name "Net-(POT3A-Pad2)") (class "Default")
      (node (ref "POT3A") (pin "2") (pinfunction "2_2") (pintype "bidirectional"))
      (node (ref "R103") (pin "2") (pinfunction "2_2") (pintype "passive"))
    )
    (net (code "53") (name "Net-(POT3B-Pad2)") (class "Default")
      (node (ref "POT3B") (pin "2") (pinfunction "2_2") (pintype "bidirectional"))
      (node (ref "R203") (pin "2") (pinfunction "2_2") (pintype "passive"))
    )
    (net (code "54") (name "Net-(POT4A-Pad2)") (class "Default")
      (node (ref "POT4A") (pin "2") (pinfunction "2_2") (pintype "bidirectional"))
      (node (ref "R104") (pin "2") (pinfunction "2_2") (pintype "passive"))
    )
    (net (code "55") (name "Net-(POT4B-Pad2)") (class "Default")
      (node (ref "POT4B") (pin "2") (pinfunction "2_2") (pintype "bidirectional"))
      (node (ref "R204") (pin "2") (pinfunction "2_2") (pintype "passive"))
    )
    (net (code "56") (name "Net-(POTMA-Pad2)") (class "Default")
      (node (ref "POTMA") (pin "2") (pinfunction "2_2") (pintype "bidirectional"))
      (node (ref "R303") (pin "2") (pinfunction "2_2") (pintype "passive"))
      (node (ref "R309") (pin "2") (pinfunction "2_2") (pintype "passive"))
    )
    (net (code "57") (name "Net-(POTMB-Pad2)") (class "Default")
      (node (ref "POTMB") (pin "2") (pinfunction "2_2") (pintype "bidirectional"))
      (node (ref "R403") (pin "2") (pinfunction "2_2") (pintype "passive"))
      (node (ref "R409") (pin "2") (pinfunction "2_2") (pintype "passive"))
    )
    (net (code "58") (name "Net-(T301-B)") (class "Default")
      (node (ref "R306") (pin "1") (pinfunction "1_1") (pintype "passive"))
      (node (ref "T301") (pin "1") (pinfunction "B_1") (pintype "passive"))
      (node (ref "T301") (pin "3") (pinfunction "C_3") (pintype "passive"))
      (node (ref "T302") (pin "1") (pinfunction "B_1") (pintype "passive"))
    )
    (net (code "59") (name "Net-(T302-E)") (class "Default")
      (node (ref "R307") (pin "2") (pinfunction "2_2") (pintype "passive"))
      (node (ref "T302") (pin "2") (pinfunction "E_2") (pintype "passive"))
    )
    (net (code "60") (name "Net-(T401-B)") (class "Default")
      (node (ref "R406") (pin "1") (pinfunction "1_1") (pintype "passive"))
      (node (ref "T401") (pin "1") (pinfunction "B_1") (pintype "passive"))
      (node (ref "T401") (pin "3") (pinfunction "C_3") (pintype "passive"))
      (node (ref "T402") (pin "1") (pinfunction "B_1") (pintype "passive"))
    )
    (net (code "61") (name "Net-(T402-E)") (class "Default")
      (node (ref "R407") (pin "2") (pinfunction "2_2") (pintype "passive"))
      (node (ref "T402") (pin "2") (pinfunction "E_2") (pintype "passive"))
    )
    (net (code "62") (name "Net-(VAC1-LDRA)") (class "Default")
      (node (ref "R106") (pin "1") (pinfunction "1_1") (pintype "passive"))
      (node (ref "R110") (pin "2") (pinfunction "2_2") (pintype "passive"))
      (node (ref "VAC1") (pin "3") (pinfunction "LDRA_3") (pintype "bidirectional"))
      (node (ref "X5") (pin "3") (pinfunction "S_3") (pintype "passive"))
    )
    (net (code "63") (name "Net-(VAC1-LED-)") (class "Default")
      (node (ref "LED1") (pin "A") (pinfunction "A_A") (pintype "passive"))
      (node (ref "VAC1") (pin "1") (pinfunction "LED-_1") (pintype "bidirectional"))
    )
    (net (code "64") (name "Net-(VAC2-LDRA)") (class "Default")
      (node (ref "R206") (pin "1") (pinfunction "1_1") (pintype "passive"))
      (node (ref "R210") (pin "2") (pinfunction "2_2") (pintype "passive"))
      (node (ref "VAC2") (pin "3") (pinfunction "LDRA_3") (pintype "bidirectional"))
      (node (ref "X5") (pin "1") (pinfunction "S_1") (pintype "passive"))
    )
    (net (code "65") (name "Net-(VAC2-LED-)") (class "Default")
      (node (ref "LED2") (pin "A") (pinfunction "A_A") (pintype "passive"))
      (node (ref "VAC2") (pin "1") (pinfunction "LED-_1") (pintype "bidirectional"))
    )
    (net (code "66") (name "Net-(X4A-S)") (class "Default")
      (node (ref "R209") (pin "2") (pinfunction "2_2") (pintype "passive"))
      (node (ref "X4") (pin "1") (pinfunction "S_1") (pintype "passive"))
    )
    (net (code "67") (name "Net-(X4C-S)") (class "Default")
      (node (ref "R109") (pin "2") (pinfunction "2_2") (pintype "passive"))
      (node (ref "X4") (pin "3") (pinfunction "S_3") (pintype "passive"))
    )
    (net (code "68") (name "unconnected-(U$3-Pad11)") (class "Default")
      (node (ref "U$3") (pin "11") (pinfunction "11_11") (pintype "passive"))
    )
    (net (code "69") (name "unconnected-(U$3-Pad12)") (class "Default")
      (node (ref "U$3") (pin "12") (pinfunction "12_12") (pintype "passive"))
    )
    (net (code "70") (name "unconnected-(U$3-Pad13)") (class "Default")
      (node (ref "U$3") (pin "13") (pinfunction "13_13") (pintype "passive"))
    )
    (net (code "71") (name "unconnected-(U$3-Pad14)") (class "Default")
      (node (ref "U$3") (pin "14") (pinfunction "14_14") (pintype "passive"))
    )
    (net (code "72") (name "unconnected-(U$3-Pad15)") (class "Default")
      (node (ref "U$3") (pin "15") (pinfunction "15_15") (pintype "passive"))
    )
    (net (code "73") (name "unconnected-(U$3-Pad16)") (class "Default")
      (node (ref "U$3") (pin "16") (pinfunction "16_16") (pintype "passive"))
    )
  )
)
